# Battery_Voltage_12v_Max.net
KiCad netlist of a schematic drawn in Altium Designer
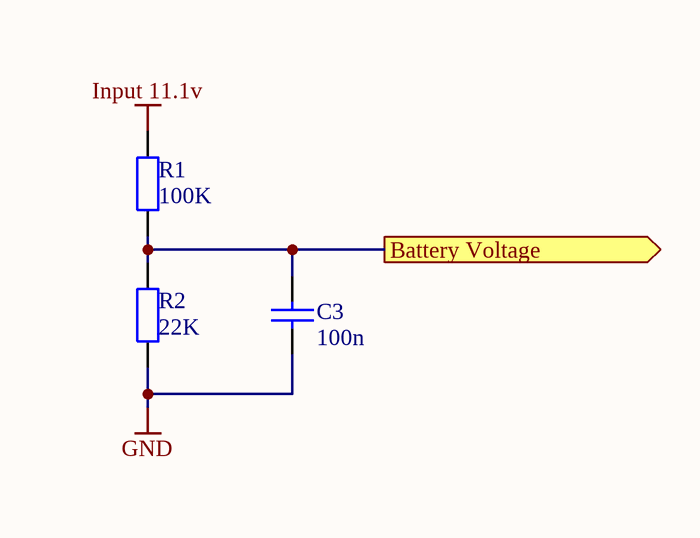
[diagram p0: Battery Voltage 12v Max.SchDoc]

(export (version "E")
  (design (tool "Eeschema 10.0.6"))
  (components
    (comp (ref "C3")
      (value "100n")
      (footprint "C0805")
      (fields (field (name "TOLERANCE") "0.1") (field (name "AUTHOR") "Willy Pietersz"))
      (libsource (lib "OurDb") (part "cap_NonPolar"))
    )
    (comp (ref "R1")
      (value "100K")
      (footprint "R0805")
      (description "Resistor")
      (fields
        (field (name "POWER") "0.25W")
        (field (name "TOLERANCE") "0.05")
        (field (name "PUBLISHER") "Altium Limited")
        (field (name "AUTHOR") "Willy Pietersz")
      )
      (libsource (lib "OurDb") (part "RESISTOR"))
    )
    (comp (ref "R2")
      (value "22K")
      (footprint "R0805")
      (description "Resistor")
      (fields
        (field (name "POWER") "0.25W")
        (field (name "TOLERANCE") "0.05")
        (field (name "PUBLISHER") "Altium Limited")
        (field (name "AUTHOR") "Willy Pietersz")
      )
      (libsource (lib "OurDb") (part "RESISTOR"))
    )
  )
  (nets
    (net (code "1") (name "/Battery Voltage") (class "Default")
      (node (ref "C3") (pin "2") (pinfunction "2_2") (pintype "passive"))
      (node (ref "R1") (pin "2") (pinfunction "2_2") (pintype "passive"))
      (node (ref "R2") (pin "1") (pinfunction "1_1") (pintype "passive"))
    )
    (net (code "2") (name "GND") (class "Default")
      (node (ref "C3") (pin "1") (pinfunction "1_1") (pintype "passive"))
      (node (ref "R2") (pin "2") (pinfunction "2_2") (pintype "passive"))
    )
    (net (code "3") (name "Input 11.1v") (class "Default")
      (node (ref "R1") (pin "1") (pinfunction "1_1") (pintype "passive"))
    )
  )
)
